# 14_-_CONNECTORS.net
KiCad netlist of a schematic drawn in Altium Designer
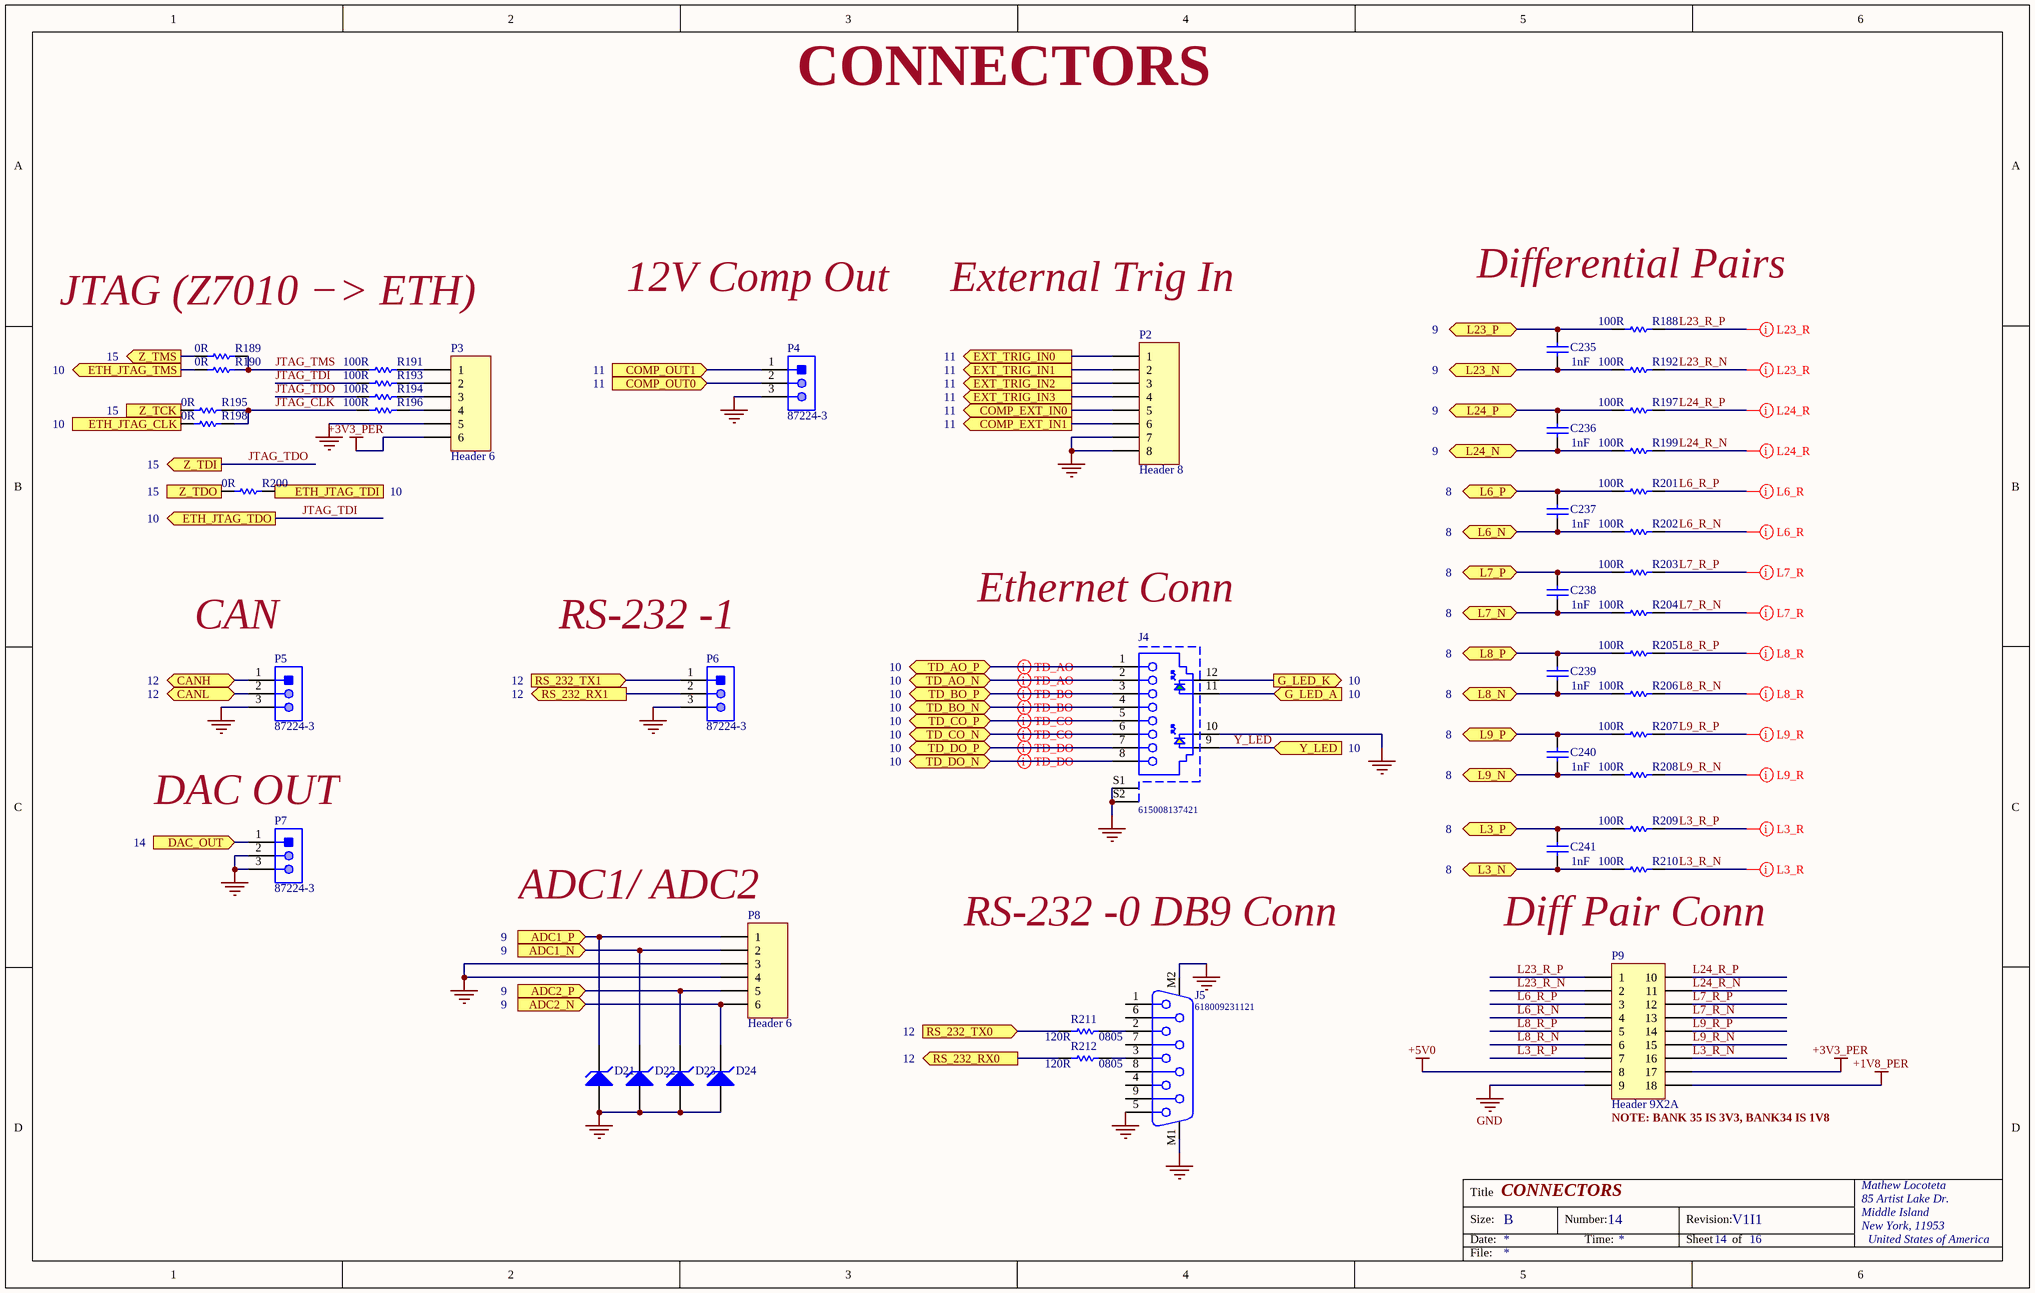
[diagram p0: [14] - CONNECTORS.SchDoc]

(export (version "E")
  (design (tool "Eeschema 10.0.6"))
  (components
    (comp (ref "C235")
      (value "1nF")
      (footprint "CAPC1005X55X25LL05T10")
      (fields (field (name "PART NUMBER") "GRM1555C1H102JA01D") (field (name "MANUFACTURER") "Murata"))
      (libsource (lib "Altium Content Vault") (part "CAP"))
    )
    (comp (ref "C236")
      (value "1nF")
      (footprint "CAPC1005X55X25LL05T10")
      (fields (field (name "PART NUMBER") "GRM1555C1H102JA01D") (field (name "MANUFACTURER") "Murata"))
      (libsource (lib "Altium Content Vault") (part "CAP"))
    )
    (comp (ref "C237")
      (value "1nF")
      (footprint "CAPC1005X55X25LL05T10")
      (fields (field (name "PART NUMBER") "GRM1555C1H102JA01D") (field (name "MANUFACTURER") "Murata"))
      (libsource (lib "Altium Content Vault") (part "CAP"))
    )
    (comp (ref "C238")
      (value "1nF")
      (footprint "CAPC1005X55X25LL05T10")
      (fields (field (name "PART NUMBER") "GRM1555C1H102JA01D") (field (name "MANUFACTURER") "Murata"))
      (libsource (lib "Altium Content Vault") (part "CAP"))
    )
    (comp (ref "C239")
      (value "1nF")
      (footprint "CAPC1005X55X25LL05T10")
      (fields (field (name "PART NUMBER") "GRM1555C1H102JA01D") (field (name "MANUFACTURER") "Murata"))
      (libsource (lib "Altium Content Vault") (part "CAP"))
    )
    (comp (ref "C240")
      (value "1nF")
      (footprint "CAPC1005X55X25LL05T10")
      (fields (field (name "PART NUMBER") "GRM1555C1H102JA01D") (field (name "MANUFACTURER") "Murata"))
      (libsource (lib "Altium Content Vault") (part "CAP"))
    )
    (comp (ref "C241")
      (value "1nF")
      (footprint "CAPC1005X55X25LL05T10")
      (fields (field (name "PART NUMBER") "GRM1555C1H102JA01D") (field (name "MANUFACTURER") "Murata"))
      (libsource (lib "Altium Content Vault") (part "CAP"))
    )
    (comp (ref "D21")
      (value "ESD5Z2.5T1G")
      (footprint "ONSC-SOD-523-2-502-01_V")
      (fields (field (name "MANUFACTURER") "On Semiconductor"))
      (libsource (lib "Altium Content Vault") (part "ONSC-K1A2-2"))
    )
    (comp (ref "D22")
      (value "ESD5Z2.5T1G")
      (footprint "ONSC-SOD-523-2-502-01_V")
      (fields (field (name "MANUFACTURER") "On Semiconductor"))
      (libsource (lib "Altium Content Vault") (part "ONSC-K1A2-2"))
    )
    (comp (ref "D23")
      (value "ESD5Z2.5T1G")
      (footprint "ONSC-SOD-523-2-502-01_V")
      (fields (field (name "MANUFACTURER") "On Semiconductor"))
      (libsource (lib "Altium Content Vault") (part "ONSC-K1A2-2"))
    )
    (comp (ref "D24")
      (value "ESD5Z2.5T1G")
      (footprint "ONSC-SOD-523-2-502-01_V")
      (fields (field (name "MANUFACTURER") "On Semiconductor"))
      (libsource (lib "Altium Content Vault") (part "ONSC-K1A2-2"))
    )
    (comp (ref "J4")
      (value "615008137421")
      (footprint "615008137421")
      (description "Modular Jack WR-MJ, Tab Up, Shielded, with LED and EMI Panel Finger, Horizontal Entry, THT, 8P8C")
      (fields (field (name "MANUFACTURER") "Wurth Elektronik") (field (name "PUBLISHER") "WurthElektronik"))
      (libsource (lib "Altium Content Vault") (part "WE-CN-1P-2F-J12_A"))
    )
    (comp (ref "J5")
      (value "618009231121")
      (footprint "618009231121")
      (description "Female PCB Connector with Hex Screw WR-DSUB, 8.08 mm, Angled, 9 pins")
      (fields (field (name "MANUFACTURER") "Wurth Elektronik") (field (name "PUBLISHER") "WurthElektronik"))
      (libsource (lib "Altium Content Vault") (part "WE-CN-2S-2F-D9"))
    )
    (comp (ref "P2")
      (value "Header 8")
      (footprint "HDR1X8")
      (description "Header, 8-Pin")
      (fields (field (name "PUBLISHER") "Altium Limited"))
      (libsource (lib "Miscellaneous Connectors") (part "Header 8"))
    )
    (comp (ref "P3")
      (value "Header 6")
      (footprint "HDR1X6")
      (description "Header, 6-Pin")
      (fields (field (name "PUBLISHER") "Altium Limited"))
      (libsource (lib "Miscellaneous Connectors") (part "Header 6"))
    )
    (comp (ref "P4")
      (value "87224-3")
      (footprint "TECO-87224-3_V")
      (fields (field (name "MANUFACTURER") "TE Connectivity"))
      (libsource (lib "Altium Content Vault") (part "CN-1P-M-R3"))
    )
    (comp (ref "P5")
      (value "87224-3")
      (footprint "TECO-87224-3_V")
      (fields (field (name "MANUFACTURER") "TE Connectivity"))
      (libsource (lib "Altium Content Vault") (part "CN-1P-M-R3"))
    )
    (comp (ref "P6")
      (value "87224-3")
      (footprint "TECO-87224-3_V")
      (fields (field (name "MANUFACTURER") "TE Connectivity"))
      (libsource (lib "Altium Content Vault") (part "CN-1P-M-R3"))
    )
    (comp (ref "P7")
      (value "87224-3")
      (footprint "TECO-87224-3_V")
      (fields (field (name "MANUFACTURER") "TE Connectivity"))
      (libsource (lib "Altium Content Vault") (part "CN-1P-M-R3"))
    )
    (comp (ref "P8")
      (value "Header 6")
      (footprint "HDR1X6")
      (description "Header, 6-Pin")
      (fields (field (name "PUBLISHER") "Altium Limited"))
      (libsource (lib "Miscellaneous Connectors") (part "Header 6"))
    )
    (comp (ref "P9")
      (value "Header 9X2A")
      (footprint "HDR2X9_CEN")
      (description "Header, 9-Pin, Dual row")
      (fields (field (name "PUBLISHER") "Altium Limited"))
      (libsource (lib "Miscellaneous Connectors") (part "Header 9X2A"))
    )
    (comp (ref "R188")
      (value "CRCW0402100RFKED")
      (footprint "RESC1005X40X25NL05T05")
      (fields (field (name "MANUFACTURER") "Vishay Dale") (field (name "PARAMETER") "100R"))
      (libsource (lib "Altium Content Vault") (part "RES"))
    )
    (comp (ref "R189")
      (value "0R")
      (footprint "R0402")
      (description "RES 0 OHM JUMPER 1/16W 0402")
      (fields
        (field (name "MANUFACTURER") "Stackpole Electronics")
        (field (name "MANUFACTURER PART NUMBER") "RMCF0402ZT0R00")
      )
      (libsource (lib "DVXC4+ ECU (2)") (part "RMCF0402ZT0R00"))
    )
    (comp (ref "R190")
      (value "0R")
      (footprint "R0402")
      (description "RES 0 OHM JUMPER 1/16W 0402")
      (fields
        (field (name "MANUFACTURER") "Stackpole Electronics")
        (field (name "MANUFACTURER PART NUMBER") "RMCF0402ZT0R00")
      )
      (libsource (lib "DVXC4+ ECU (2)") (part "RMCF0402ZT0R00"))
    )
    (comp (ref "R191")
      (value "CRCW0402100RFKED")
      (footprint "RESC1005X40X25NL05T05")
      (fields (field (name "MANUFACTURER") "Vishay Dale") (field (name "PARAMETER") "100R"))
      (libsource (lib "Altium Content Vault") (part "RES"))
    )
    (comp (ref "R192")
      (value "CRCW0402100RFKED")
      (footprint "RESC1005X40X25NL05T05")
      (fields (field (name "MANUFACTURER") "Vishay Dale") (field (name "PARAMETER") "100R"))
      (libsource (lib "Altium Content Vault") (part "RES"))
    )
    (comp (ref "R193")
      (value "CRCW0402100RFKED")
      (footprint "RESC1005X40X25NL05T05")
      (fields (field (name "MANUFACTURER") "Vishay Dale") (field (name "PARAMETER") "100R"))
      (libsource (lib "Altium Content Vault") (part "RES"))
    )
    (comp (ref "R194")
      (value "CRCW0402100RFKED")
      (footprint "RESC1005X40X25NL05T05")
      (fields (field (name "MANUFACTURER") "Vishay Dale") (field (name "PARAMETER") "100R"))
      (libsource (lib "Altium Content Vault") (part "RES"))
    )
    (comp (ref "R195")
      (value "0R")
      (footprint "R0402")
      (description "RES 0 OHM JUMPER 1/16W 0402")
      (fields
        (field (name "MANUFACTURER") "Stackpole Electronics")
        (field (name "MANUFACTURER PART NUMBER") "RMCF0402ZT0R00")
      )
      (libsource (lib "DVXC4+ ECU (2)") (part "RMCF0402ZT0R00"))
    )
    (comp (ref "R196")
      (value "CRCW0402100RFKED")
      (footprint "RESC1005X40X25NL05T05")
      (fields (field (name "MANUFACTURER") "Vishay Dale") (field (name "PARAMETER") "100R"))
      (libsource (lib "Altium Content Vault") (part "RES"))
    )
    (comp (ref "R197")
      (value "CRCW0402100RFKED")
      (footprint "RESC1005X40X25NL05T05")
      (fields (field (name "MANUFACTURER") "Vishay Dale") (field (name "PARAMETER") "100R"))
      (libsource (lib "Altium Content Vault") (part "RES"))
    )
    (comp (ref "R198")
      (value "0R")
      (footprint "R0402")
      (description "RES 0 OHM JUMPER 1/16W 0402")
      (fields
        (field (name "MANUFACTURER") "Stackpole Electronics")
        (field (name "MANUFACTURER PART NUMBER") "RMCF0402ZT0R00")
      )
      (libsource (lib "DVXC4+ ECU (2)") (part "RMCF0402ZT0R00"))
    )
    (comp (ref "R199")
      (value "CRCW0402100RFKED")
      (footprint "RESC1005X40X25NL05T05")
      (fields (field (name "MANUFACTURER") "Vishay Dale") (field (name "PARAMETER") "100R"))
      (libsource (lib "Altium Content Vault") (part "RES"))
    )
    (comp (ref "R200")
      (value "0R")
      (footprint "R0402")
      (description "RES 0 OHM JUMPER 1/16W 0402")
      (fields
        (field (name "MANUFACTURER") "Stackpole Electronics")
        (field (name "MANUFACTURER PART NUMBER") "RMCF0402ZT0R00")
      )
      (libsource (lib "DVXC4+ ECU (2)") (part "RMCF0402ZT0R00"))
    )
    (comp (ref "R201")
      (value "CRCW0402100RFKED")
      (footprint "RESC1005X40X25NL05T05")
      (fields (field (name "MANUFACTURER") "Vishay Dale") (field (name "PARAMETER") "100R"))
      (libsource (lib "Altium Content Vault") (part "RES"))
    )
    (comp (ref "R202")
      (value "CRCW0402100RFKED")
      (footprint "RESC1005X40X25NL05T05")
      (fields (field (name "MANUFACTURER") "Vishay Dale") (field (name "PARAMETER") "100R"))
      (libsource (lib "Altium Content Vault") (part "RES"))
    )
    (comp (ref "R203")
      (value "CRCW0402100RFKED")
      (footprint "RESC1005X40X25NL05T05")
      (fields (field (name "MANUFACTURER") "Vishay Dale") (field (name "PARAMETER") "100R"))
      (libsource (lib "Altium Content Vault") (part "RES"))
    )
    (comp (ref "R204")
      (value "CRCW0402100RFKED")
      (footprint "RESC1005X40X25NL05T05")
      (fields (field (name "MANUFACTURER") "Vishay Dale") (field (name "PARAMETER") "100R"))
      (libsource (lib "Altium Content Vault") (part "RES"))
    )
    (comp (ref "R205")
      (value "CRCW0402100RFKED")
      (footprint "RESC1005X40X25NL05T05")
      (fields (field (name "MANUFACTURER") "Vishay Dale") (field (name "PARAMETER") "100R"))
      (libsource (lib "Altium Content Vault") (part "RES"))
    )
    (comp (ref "R206")
      (value "CRCW0402100RFKED")
      (footprint "RESC1005X40X25NL05T05")
      (fields (field (name "MANUFACTURER") "Vishay Dale") (field (name "PARAMETER") "100R"))
      (libsource (lib "Altium Content Vault") (part "RES"))
    )
    (comp (ref "R207")
      (value "CRCW0402100RFKED")
      (footprint "RESC1005X40X25NL05T05")
      (fields (field (name "MANUFACTURER") "Vishay Dale") (field (name "PARAMETER") "100R"))
      (libsource (lib "Altium Content Vault") (part "RES"))
    )
    (comp (ref "R208")
      (value "CRCW0402100RFKED")
      (footprint "RESC1005X40X25NL05T05")
      (fields (field (name "MANUFACTURER") "Vishay Dale") (field (name "PARAMETER") "100R"))
      (libsource (lib "Altium Content Vault") (part "RES"))
    )
    (comp (ref "R209")
      (value "CRCW0402100RFKED")
      (footprint "RESC1005X40X25NL05T05")
      (fields (field (name "MANUFACTURER") "Vishay Dale") (field (name "PARAMETER") "100R"))
      (libsource (lib "Altium Content Vault") (part "RES"))
    )
    (comp (ref "R210")
      (value "CRCW0402100RFKED")
      (footprint "RESC1005X40X25NL05T05")
      (fields (field (name "MANUFACTURER") "Vishay Dale") (field (name "PARAMETER") "100R"))
      (libsource (lib "Altium Content Vault") (part "RES"))
    )
    (comp (ref "R211")
      (value "120R")
      (footprint "RESC2013X50X30LL20T20")
      (fields
        (field (name "PART NUMBER") "CRCW0805120RJNEA")
        (field (name "MANUFACTURER") "Vishay Dale")
        (field (name "CASE") "0805")
      )
      (libsource (lib "Altium Content Vault") (part "RES"))
    )
    (comp (ref "R212")
      (value "120R")
      (footprint "RESC2013X50X30LL20T20")
      (fields
        (field (name "PART NUMBER") "CRCW0805120RJNEA")
        (field (name "MANUFACTURER") "Vishay Dale")
        (field (name "CASE") "0805")
      )
      (libsource (lib "Altium Content Vault") (part "RES"))
    )
  )
  (nets
    (net (code "1") (name "+1V8_PER") (class "Default")
      (node (ref "P9") (pin "18") (pinfunction "18_18") (pintype "passive"))
    )
    (net (code "2") (name "+3V3_PER") (class "Default")
      (node (ref "P3") (pin "6") (pinfunction "6_6") (pintype "passive"))
      (node (ref "P9") (pin "17") (pinfunction "17_17") (pintype "passive"))
    )
    (net (code "3") (name "+5V0") (class "Default")
      (node (ref "P9") (pin "8") (pinfunction "8_8") (pintype "passive"))
    )
    (net (code "4") (name "/ADC1_N") (class "Default")
      (node (ref "D22") (pin "1") (pinfunction "K_1") (pintype "passive"))
      (node (ref "P8") (pin "2") (pinfunction "2_2") (pintype "passive"))
    )
    (net (code "5") (name "/ADC1_P") (class "Default")
      (node (ref "D21") (pin "1") (pinfunction "K_1") (pintype "passive"))
      (node (ref "P8") (pin "1") (pinfunction "1_1") (pintype "passive"))
    )
    (net (code "6") (name "/ADC2_N") (class "Default")
      (node (ref "D24") (pin "1") (pinfunction "K_1") (pintype "passive"))
      (node (ref "P8") (pin "6") (pinfunction "6_6") (pintype "passive"))
    )
    (net (code "7") (name "/ADC2_P") (class "Default")
      (node (ref "D23") (pin "1") (pinfunction "K_1") (pintype "passive"))
      (node (ref "P8") (pin "5") (pinfunction "5_5") (pintype "passive"))
    )
    (net (code "8") (name "/CANH") (class "Default")
      (node (ref "P5") (pin "1") (pinfunction "1_1") (pintype "passive"))
    )
    (net (code "9") (name "/CANL") (class "Default")
      (node (ref "P5") (pin "2") (pinfunction "2_2") (pintype "passive"))
    )
    (net (code "10") (name "/COMP_EXT_IN0") (class "Default")
      (node (ref "P2") (pin "5") (pinfunction "5_5") (pintype "passive"))
    )
    (net (code "11") (name "/COMP_EXT_IN1") (class "Default")
      (node (ref "P2") (pin "6") (pinfunction "6_6") (pintype "passive"))
    )
    (net (code "12") (name "/COMP_OUT0") (class "Default")
      (node (ref "P4") (pin "2") (pinfunction "2_2") (pintype "passive"))
    )
    (net (code "13") (name "/COMP_OUT1") (class "Default")
      (node (ref "P4") (pin "1") (pinfunction "1_1") (pintype "passive"))
    )
    (net (code "14") (name "/DAC_OUT") (class "Default")
      (node (ref "P7") (pin "1") (pinfunction "1_1") (pintype "passive"))
    )
    (net (code "15") (name "/ETH_JTAG_CLK") (class "Default")
      (node (ref "R198") (pin "1") (pinfunction "1_1") (pintype "passive"))
    )
    (net (code "16") (name "/ETH_JTAG_TDI") (class "Default")
      (node (ref "R200") (pin "2") (pinfunction "2_2") (pintype "passive"))
    )
    (net (code "17") (name "/ETH_JTAG_TMS") (class "Default")
      (node (ref "R190") (pin "1") (pinfunction "1_1") (pintype "passive"))
    )
    (net (code "18") (name "/EXT_TRIG_IN0") (class "Default")
      (node (ref "P2") (pin "1") (pinfunction "1_1") (pintype "passive"))
    )
    (net (code "19") (name "/EXT_TRIG_IN1") (class "Default")
      (node (ref "P2") (pin "2") (pinfunction "2_2") (pintype "passive"))
    )
    (net (code "20") (name "/EXT_TRIG_IN2") (class "Default")
      (node (ref "P2") (pin "3") (pinfunction "3_3") (pintype "passive"))
    )
    (net (code "21") (name "/EXT_TRIG_IN3") (class "Default")
      (node (ref "P2") (pin "4") (pinfunction "4_4") (pintype "passive"))
    )
    (net (code "22") (name "/G_LED_A") (class "Default")
      (node (ref "J4") (pin "11") (pinfunction "11_11") (pintype "passive"))
    )
    (net (code "23") (name "/G_LED_K") (class "Default")
      (node (ref "J4") (pin "12") (pinfunction "12_12") (pintype "passive"))
    )
    (net (code "24") (name "/JTAG_CLK") (class "Default")
      (node (ref "R195") (pin "2") (pinfunction "2_2") (pintype "passive"))
      (node (ref "R196") (pin "1") (pinfunction "1_1") (pintype "passive"))
      (node (ref "R198") (pin "2") (pinfunction "2_2") (pintype "passive"))
    )
    (net (code "25") (name "/JTAG_TDI") (class "Default")
      (node (ref "R193") (pin "1") (pinfunction "1_1") (pintype "passive"))
    )
    (net (code "26") (name "/JTAG_TDO") (class "Default")
      (node (ref "R194") (pin "1") (pinfunction "1_1") (pintype "passive"))
    )
    (net (code "27") (name "/JTAG_TMS") (class "Default")
      (node (ref "R189") (pin "2") (pinfunction "2_2") (pintype "passive"))
      (node (ref "R190") (pin "2") (pinfunction "2_2") (pintype "passive"))
      (node (ref "R191") (pin "1") (pinfunction "1_1") (pintype "passive"))
    )
    (net (code "28") (name "/L3_N") (class "Default")
      (node (ref "C241") (pin "1") (pinfunction "1_1") (pintype "passive"))
      (node (ref "R210") (pin "1") (pinfunction "1_1") (pintype "passive"))
    )
    (net (code "29") (name "/L3_P") (class "Default")
      (node (ref "C241") (pin "2") (pinfunction "2_2") (pintype "passive"))
      (node (ref "R209") (pin "1") (pinfunction "1_1") (pintype "passive"))
    )
    (net (code "30") (name "/L3_R_N") (class "Default")
      (node (ref "P9") (pin "16") (pinfunction "16_16") (pintype "passive"))
      (node (ref "R210") (pin "2") (pinfunction "2_2") (pintype "passive"))
    )
    (net (code "31") (name "/L3_R_P") (class "Default")
      (node (ref "P9") (pin "7") (pinfunction "7_7") (pintype "passive"))
      (node (ref "R209") (pin "2") (pinfunction "2_2") (pintype "passive"))
    )
    (net (code "32") (name "/L6_N") (class "Default")
      (node (ref "C237") (pin "1") (pinfunction "1_1") (pintype "passive"))
      (node (ref "R202") (pin "1") (pinfunction "1_1") (pintype "passive"))
    )
    (net (code "33") (name "/L6_P") (class "Default")
      (node (ref "C237") (pin "2") (pinfunction "2_2") (pintype "passive"))
      (node (ref "R201") (pin "1") (pinfunction "1_1") (pintype "passive"))
    )
    (net (code "34") (name "/L6_R_N") (class "Default")
      (node (ref "P9") (pin "4") (pinfunction "4_4") (pintype "passive"))
      (node (ref "R202") (pin "2") (pinfunction "2_2") (pintype "passive"))
    )
    (net (code "35") (name "/L6_R_P") (class "Default")
      (node (ref "P9") (pin "3") (pinfunction "3_3") (pintype "passive"))
      (node (ref "R201") (pin "2") (pinfunction "2_2") (pintype "passive"))
    )
    (net (code "36") (name "/L7_N") (class "Default")
      (node (ref "C238") (pin "1") (pinfunction "1_1") (pintype "passive"))
      (node (ref "R204") (pin "1") (pinfunction "1_1") (pintype "passive"))
    )
    (net (code "37") (name "/L7_P") (class "Default")
      (node (ref "C238") (pin "2") (pinfunction "2_2") (pintype "passive"))
      (node (ref "R203") (pin "1") (pinfunction "1_1") (pintype "passive"))
    )
    (net (code "38") (name "/L7_R_N") (class "Default")
      (node (ref "P9") (pin "13") (pinfunction "13_13") (pintype "passive"))
      (node (ref "R204") (pin "2") (pinfunction "2_2") (pintype "passive"))
    )
    (net (code "39") (name "/L7_R_P") (class "Default")
      (node (ref "P9") (pin "12") (pinfunction "12_12") (pintype "passive"))
      (node (ref "R203") (pin "2") (pinfunction "2_2") (pintype "passive"))
    )
    (net (code "40") (name "/L8_N") (class "Default")
      (node (ref "C239") (pin "1") (pinfunction "1_1") (pintype "passive"))
      (node (ref "R206") (pin "1") (pinfunction "1_1") (pintype "passive"))
    )
    (net (code "41") (name "/L8_P") (class "Default")
      (node (ref "C239") (pin "2") (pinfunction "2_2") (pintype "passive"))
      (node (ref "R205") (pin "1") (pinfunction "1_1") (pintype "passive"))
    )
    (net (code "42") (name "/L8_R_N") (class "Default")
      (node (ref "P9") (pin "6") (pinfunction "6_6") (pintype "passive"))
      (node (ref "R206") (pin "2") (pinfunction "2_2") (pintype "passive"))
    )
    (net (code "43") (name "/L8_R_P") (class "Default")
      (node (ref "P9") (pin "5") (pinfunction "5_5") (pintype "passive"))
      (node (ref "R205") (pin "2") (pinfunction "2_2") (pintype "passive"))
    )
    (net (code "44") (name "/L9_N") (class "Default")
      (node (ref "C240") (pin "1") (pinfunction "1_1") (pintype "passive"))
      (node (ref "R208") (pin "1") (pinfunction "1_1") (pintype "passive"))
    )
    (net (code "45") (name "/L9_P") (class "Default")
      (node (ref "C240") (pin "2") (pinfunction "2_2") (pintype "passive"))
      (node (ref "R207") (pin "1") (pinfunction "1_1") (pintype "passive"))
    )
    (net (code "46") (name "/L9_R_N") (class "Default")
      (node (ref "P9") (pin "15") (pinfunction "15_15") (pintype "passive"))
      (node (ref "R208") (pin "2") (pinfunction "2_2") (pintype "passive"))
    )
    (net (code "47") (name "/L9_R_P") (class "Default")
      (node (ref "P9") (pin "14") (pinfunction "14_14") (pintype "passive"))
      (node (ref "R207") (pin "2") (pinfunction "2_2") (pintype "passive"))
    )
    (net (code "48") (name "/L23_N") (class "Default")
      (node (ref "C235") (pin "1") (pinfunction "1_1") (pintype "passive"))
      (node (ref "R192") (pin "1") (pinfunction "1_1") (pintype "passive"))
    )
    (net (code "49") (name "/L23_P") (class "Default")
      (node (ref "C235") (pin "2") (pinfunction "2_2") (pintype "passive"))
      (node (ref "R188") (pin "1") (pinfunction "1_1") (pintype "passive"))
    )
    (net (code "50") (name "/L23_R_N") (class "Default")
      (node (ref "P9") (pin "2") (pinfunction "2_2") (pintype "passive"))
      (node (ref "R192") (pin "2") (pinfunction "2_2") (pintype "passive"))
    )
    (net (code "51") (name "/L23_R_P") (class "Default")
      (node (ref "P9") (pin "1") (pinfunction "1_1") (pintype "passive"))
      (node (ref "R188") (pin "2") (pinfunction "2_2") (pintype "passive"))
    )
    (net (code "52") (name "/L24_N") (class "Default")
      (node (ref "C236") (pin "1") (pinfunction "1_1") (pintype "passive"))
      (node (ref "R199") (pin "1") (pinfunction "1_1") (pintype "passive"))
    )
    (net (code "53") (name "/L24_P") (class "Default")
      (node (ref "C236") (pin "2") (pinfunction "2_2") (pintype "passive"))
      (node (ref "R197") (pin "1") (pinfunction "1_1") (pintype "passive"))
    )
    (net (code "54") (name "/L24_R_N") (class "Default")
      (node (ref "P9") (pin "11") (pinfunction "11_11") (pintype "passive"))
      (node (ref "R199") (pin "2") (pinfunction "2_2") (pintype "passive"))
    )
    (net (code "55") (name "/L24_R_P") (class "Default")
      (node (ref "P9") (pin "10") (pinfunction "10_10") (pintype "passive"))
      (node (ref "R197") (pin "2") (pinfunction "2_2") (pintype "passive"))
    )
    (net (code "57") (name "/RS_232_RX0") (class "Default")
      (node (ref "R212") (pin "1") (pinfunction "1_1") (pintype "passive"))
    )
    (net (code "58") (name "/RS_232_RX1") (class "Default")
      (node (ref "P6") (pin "2") (pinfunction "2_2") (pintype "passive"))
    )
    (net (code "59") (name "/RS_232_TX0") (class "Default")
      (node (ref "R211") (pin "1") (pinfunction "1_1") (pintype "passive"))
    )
    (net (code "60") (name "/RS_232_TX1") (class "Default")
      (node (ref "P6") (pin "1") (pinfunction "1_1") (pintype "passive"))
    )
    (net (code "61") (name "/TD_AO_N") (class "Default")
      (node (ref "J4") (pin "2") (pinfunction "2_2") (pintype "passive"))
    )
    (net (code "62") (name "/TD_AO_P") (class "Default")
      (node (ref "J4") (pin "1") (pinfunction "1_1") (pintype "passive"))
    )
    (net (code "63") (name "/TD_BO_N") (class "Default")
      (node (ref "J4") (pin "4") (pinfunction "4_4") (pintype "passive"))
    )
    (net (code "64") (name "/TD_BO_P") (class "Default")
      (node (ref "J4") (pin "3") (pinfunction "3_3") (pintype "passive"))
    )
    (net (code "65") (name "/TD_CO_N") (class "Default")
      (node (ref "J4") (pin "6") (pinfunction "6_6") (pintype "passive"))
    )
    (net (code "66") (name "/TD_CO_P") (class "Default")
      (node (ref "J4") (pin "5") (pinfunction "5_5") (pintype "passive"))
    )
    (net (code "67") (name "/TD_DO_N") (class "Default")
      (node (ref "J4") (pin "8") (pinfunction "8_8") (pintype "passive"))
    )
    (net (code "68") (name "/TD_DO_P") (class "Default")
      (node (ref "J4") (pin "7") (pinfunction "7_7") (pintype "passive"))
    )
    (net (code "69") (name "/Y_LED") (class "Default")
      (node (ref "J4") (pin "9") (pinfunction "9_9") (pintype "passive"))
    )
    (net (code "70") (name "/Z_TCK") (class "Default")
      (node (ref "R195") (pin "1") (pinfunction "1_1") (pintype "passive"))
    )
    (net (code "71") (name "/Z_TDO") (class "Default")
      (node (ref "R200") (pin "1") (pinfunction "1_1") (pintype "passive"))
    )
    (net (code "72") (name "/Z_TMS") (class "Default")
      (node (ref "R189") (pin "1") (pinfunction "1_1") (pintype "passive"))
    )
    (net (code "73") (name "GND") (class "Default")
      (node (ref "D21") (pin "2") (pinfunction "A_2") (pintype "passive"))
      (node (ref "D22") (pin "2") (pinfunction "A_2") (pintype "passive"))
      (node (ref "D23") (pin "2") (pinfunction "A_2") (pintype "passive"))
      (node (ref "D24") (pin "2") (pinfunction "A_2") (pintype "passive"))
      (node (ref "J4") (pin "10") (pinfunction "10_10") (pintype "passive"))
      (node (ref "J4") (pin "S1") (pinfunction "S1_S1") (pintype "passive"))
      (node (ref "J4") (pin "S2") (pinfunction "S2_S2") (pintype "passive"))
      (node (ref "J5") (pin "5") (pinfunction "5_5") (pintype "passive"))
      (node (ref "J5") (pin "M1") (pinfunction "M1_M1") (pintype "passive"))
      (node (ref "J5") (pin "M2") (pinfunction "M2_M2") (pintype "passive"))
      (node (ref "P2") (pin "7") (pinfunction "7_7") (pintype "passive"))
      (node (ref "P2") (pin "8") (pinfunction "8_8") (pintype "passive"))
      (node (ref "P3") (pin "5") (pinfunction "5_5") (pintype "passive"))
      (node (ref "P4") (pin "3") (pinfunction "3_3") (pintype "passive"))
      (node (ref "P5") (pin "3") (pinfunction "3_3") (pintype "passive"))
      (node (ref "P6") (pin "3") (pinfunction "3_3") (pintype "passive"))
      (node (ref "P7") (pin "2") (pinfunction "2_2") (pintype "passive"))
      (node (ref "P7") (pin "3") (pinfunction "3_3") (pintype "passive"))
      (node (ref "P8") (pin "3") (pinfunction "3_3") (pintype "passive"))
      (node (ref "P8") (pin "4") (pinfunction "4_4") (pintype "passive"))
      (node (ref "P9") (pin "9") (pinfunction "9_9") (pintype "passive"))
    )
    (net (code "74") (name "Net-(J5-Pad2)") (class "Default")
      (node (ref "J5") (pin "2") (pinfunction "2_2") (pintype "passive"))
      (node (ref "R211") (pin "2") (pinfunction "2_2") (pintype "passive"))
    )
    (net (code "75") (name "Net-(J5-Pad3)") (class "Default")
      (node (ref "J5") (pin "3") (pinfunction "3_3") (pintype "passive"))
      (node (ref "R212") (pin "2") (pinfunction "2_2") (pintype "passive"))
    )
    (net (code "76") (name "Net-(P3-Pad1)") (class "Default")
      (node (ref "P3") (pin "1") (pinfunction "1_1") (pintype "passive"))
      (node (ref "R191") (pin "2") (pinfunction "2_2") (pintype "passive"))
    )
    (net (code "77") (name "Net-(P3-Pad2)") (class "Default")
      (node (ref "P3") (pin "2") (pinfunction "2_2") (pintype "passive"))
      (node (ref "R193") (pin "2") (pinfunction "2_2") (pintype "passive"))
    )
    (net (code "78") (name "Net-(P3-Pad3)") (class "Default")
      (node (ref "P3") (pin "3") (pinfunction "3_3") (pintype "passive"))
      (node (ref "R194") (pin "2") (pinfunction "2_2") (pintype "passive"))
    )
    (net (code "79") (name "Net-(P3-Pad4)") (class "Default")
      (node (ref "P3") (pin "4") (pinfunction "4_4") (pintype "passive"))
      (node (ref "R196") (pin "2") (pinfunction "2_2") (pintype "passive"))
    )
    (net (code "80") (name "unconnected-(J5-Pad1)") (class "Default")
      (node (ref "J5") (pin "1") (pinfunction "1_1") (pintype "passive"))
    )
    (net (code "81") (name "unconnected-(J5-Pad4)") (class "Default")
      (node (ref "J5") (pin "4") (pinfunction "4_4") (pintype "passive"))
    )
    (net (code "82") (name "unconnected-(J5-Pad6)") (class "Default")
      (node (ref "J5") (pin "6") (pinfunction "6_6") (pintype "passive"))
    )
    (net (code "83") (name "unconnected-(J5-Pad7)") (class "Default")
      (node (ref "J5") (pin "7") (pinfunction "7_7") (pintype "passive"))
    )
    (net (code "84") (name "unconnected-(J5-Pad8)") (class "Default")
      (node (ref "J5") (pin "8") (pinfunction "8_8") (pintype "passive"))
    )
    (net (code "85") (name "unconnected-(J5-Pad9)") (class "Default")
      (node (ref "J5") (pin "9") (pinfunction "9_9") (pintype "passive"))
    )
  )
)
